# led-panel.net
KiCad netlist of a schematic drawn in EAGLE
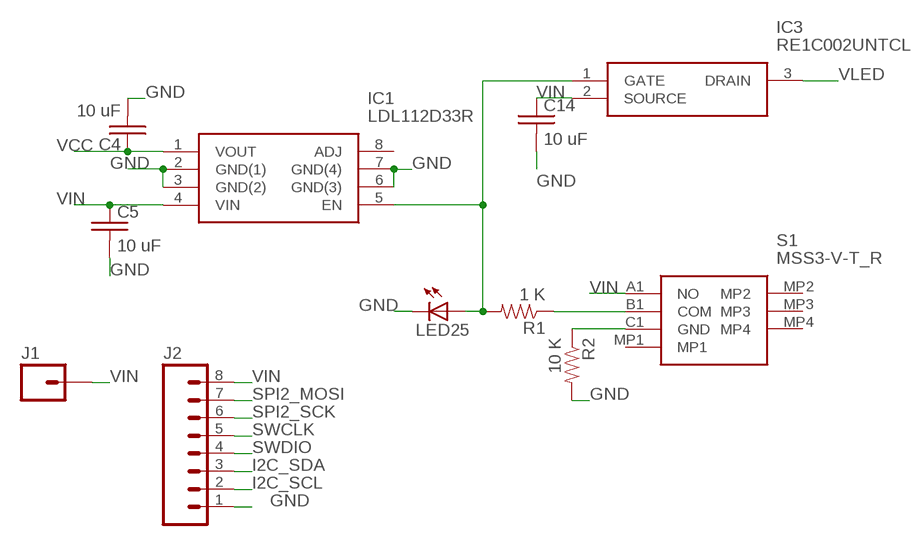
[diagram p0: schematic, sheet 1]
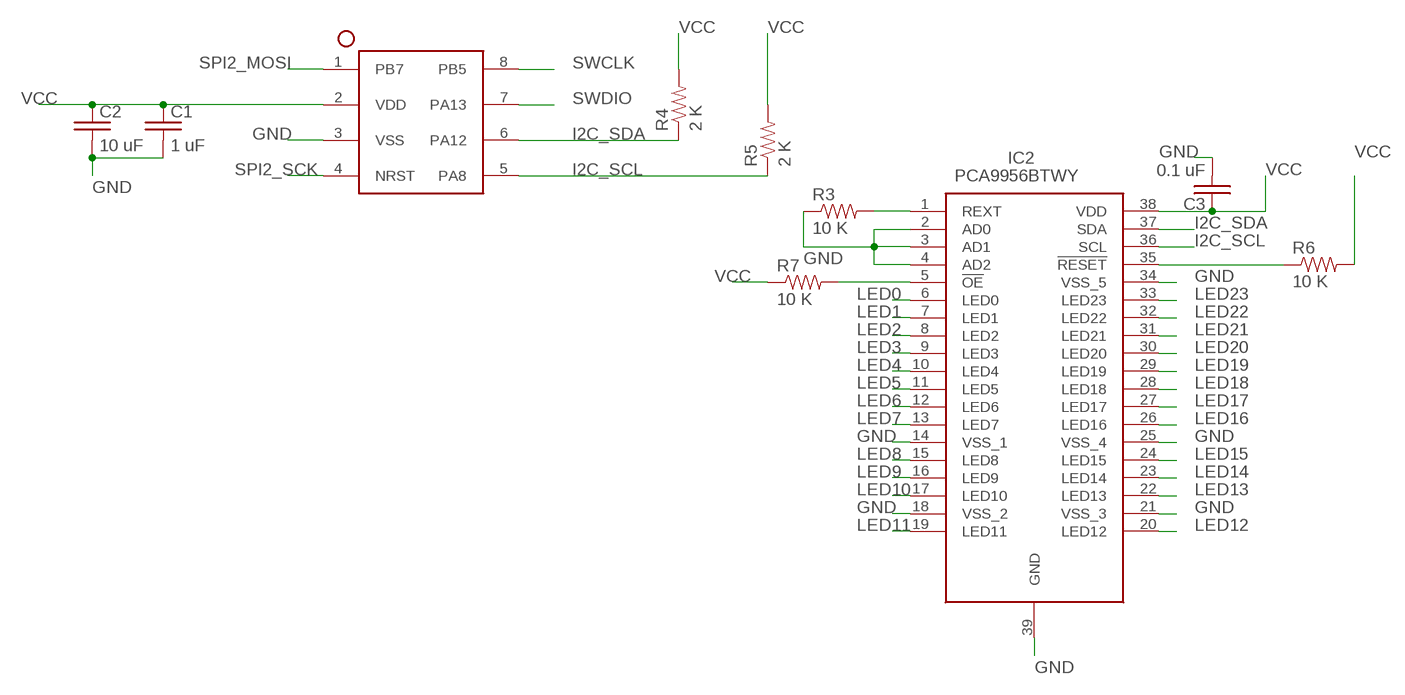
[diagram p1: schematic, sheet 2]
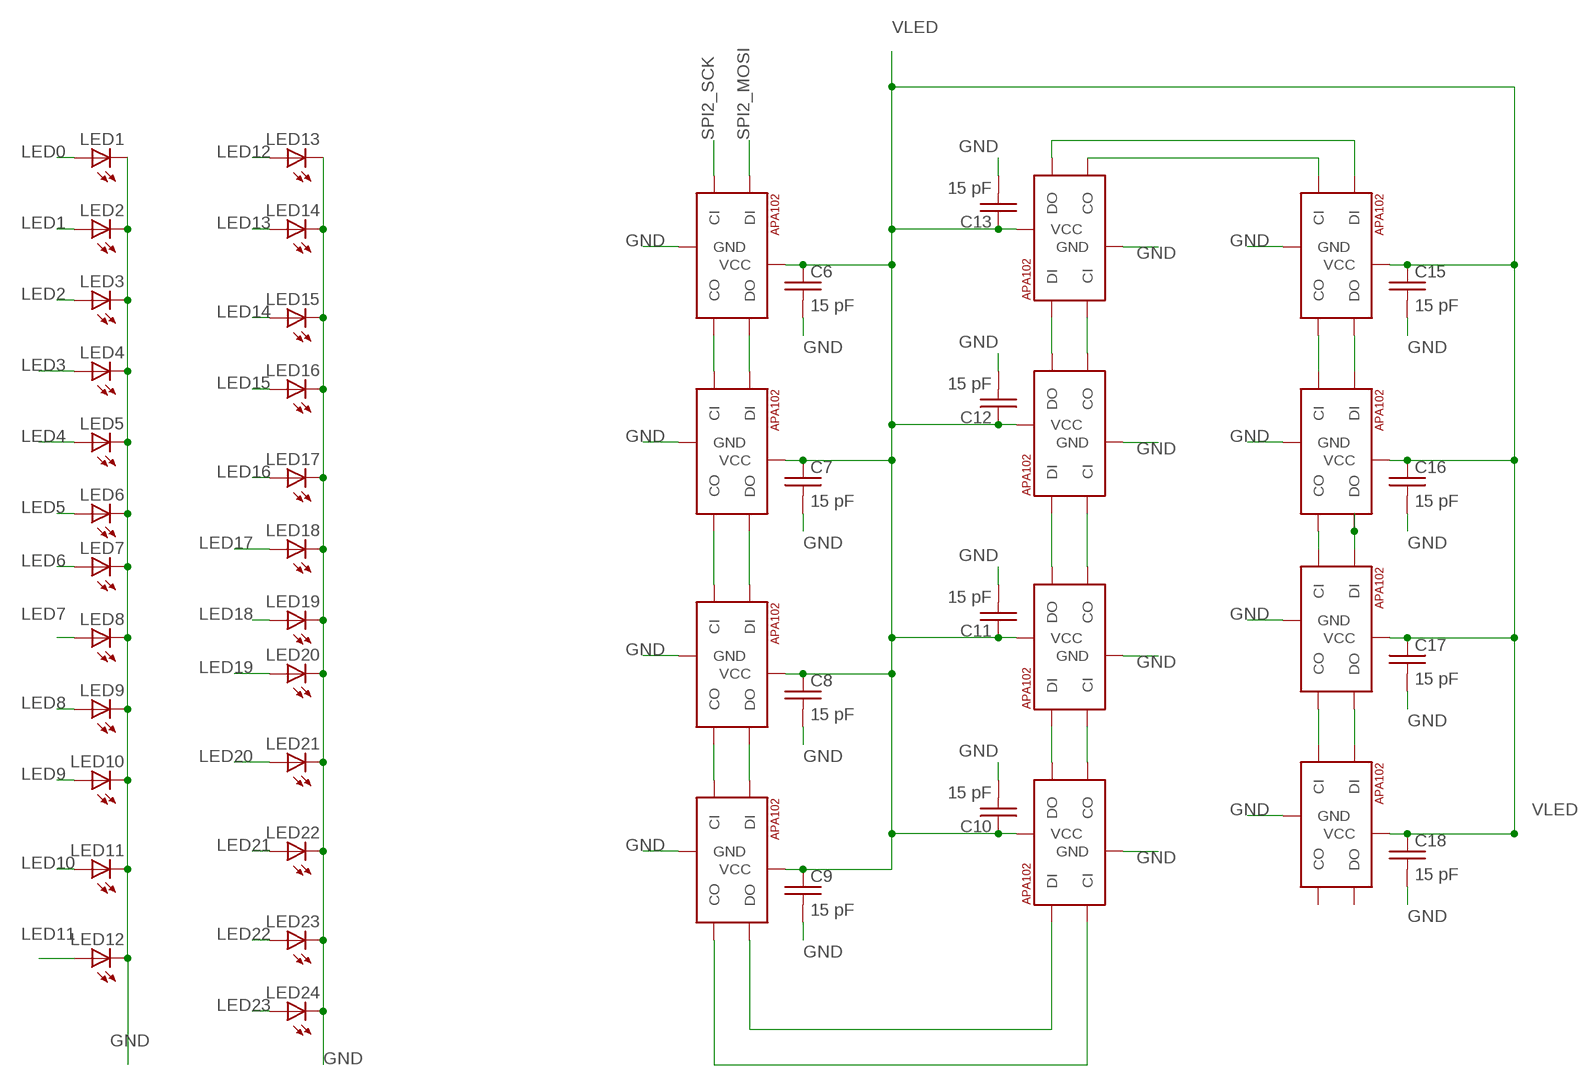
[diagram p2: schematic, sheet 3]
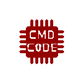
[diagram p3: schematic, sheet 4]

(export (version "E")
  (design (tool "Eeschema 10.0.6"))
  (components
    (comp (ref "U$3")
      (value "CMD_C0DE_LOGOCMD_CODE_LOGO_TOP_COPPER")
      (footprint "eagle-import:CMD_C0DE_LOGO_TOP_COPPER")
      (libsource (lib "eagle-import") (part "CMD_C0DE_LOGOCMD_CODE_LOGO_TOP_COPPER"))
    )
    (comp (ref "C6")
      (value "15 pF")
      (footprint "eagle-import:C0805K")
      (libsource (lib "eagle-import") (part "C-USC0805K"))
    )
    (comp (ref "C7")
      (value "15 pF")
      (footprint "eagle-import:C0805K")
      (libsource (lib "eagle-import") (part "C-USC0805K"))
    )
    (comp (ref "C8")
      (value "15 pF")
      (footprint "eagle-import:C0805K")
      (libsource (lib "eagle-import") (part "C-USC0805K"))
    )
    (comp (ref "C9")
      (value "15 pF")
      (footprint "eagle-import:C0805K")
      (libsource (lib "eagle-import") (part "C-USC0805K"))
    )
    (comp (ref "C10")
      (value "15 pF")
      (footprint "eagle-import:C0805K")
      (libsource (lib "eagle-import") (part "C-USC0805K"))
    )
    (comp (ref "C11")
      (value "15 pF")
      (footprint "eagle-import:C0805K")
      (libsource (lib "eagle-import") (part "C-USC0805K"))
    )
    (comp (ref "C12")
      (value "15 pF")
      (footprint "eagle-import:C0805K")
      (libsource (lib "eagle-import") (part "C-USC0805K"))
    )
    (comp (ref "C13")
      (value "15 pF")
      (footprint "eagle-import:C0805K")
      (libsource (lib "eagle-import") (part "C-USC0805K"))
    )
    (comp (ref "C15")
      (value "15 pF")
      (footprint "eagle-import:C0805K")
      (libsource (lib "eagle-import") (part "C-USC0805K"))
    )
    (comp (ref "C16")
      (value "15 pF")
      (footprint "eagle-import:C0805K")
      (libsource (lib "eagle-import") (part "C-USC0805K"))
    )
    (comp (ref "C17")
      (value "15 pF")
      (footprint "eagle-import:C0805K")
      (libsource (lib "eagle-import") (part "C-USC0805K"))
    )
    (comp (ref "C18")
      (value "15 pF")
      (footprint "eagle-import:C0805K")
      (libsource (lib "eagle-import") (part "C-USC0805K"))
    )
    (comp (ref "LED1")
      (value "LEDXZCFBB53W-8VF-2MA-LED")
      (footprint "eagle-import:LEDC1606X95N")
      (libsource (lib "eagle-import") (part "LEDXZCFBB53W-8VF-2MA-LED"))
    )
    (comp (ref "LED2")
      (value "LEDXZCFBB53W-8VF-2MA-LED")
      (footprint "eagle-import:LEDC1606X95N")
      (libsource (lib "eagle-import") (part "LEDXZCFBB53W-8VF-2MA-LED"))
    )
    (comp (ref "LED3")
      (value "LEDXZCFBB53W-8VF-2MA-LED")
      (footprint "eagle-import:LEDC1606X95N")
      (libsource (lib "eagle-import") (part "LEDXZCFBB53W-8VF-2MA-LED"))
    )
    (comp (ref "LED4")
      (value "LEDXZCFBB53W-8VF-2MA-LED")
      (footprint "eagle-import:LEDC1606X95N")
      (libsource (lib "eagle-import") (part "LEDXZCFBB53W-8VF-2MA-LED"))
    )
    (comp (ref "LED5")
      (value "LEDXZCFBB53W-8VF-2MA-LED")
      (footprint "eagle-import:LEDC1606X95N")
      (libsource (lib "eagle-import") (part "LEDXZCFBB53W-8VF-2MA-LED"))
    )
    (comp (ref "LED6")
      (value "LEDXZCFBB53W-8VF-2MA-LED")
      (footprint "eagle-import:LEDC1606X95N")
      (libsource (lib "eagle-import") (part "LEDXZCFBB53W-8VF-2MA-LED"))
    )
    (comp (ref "LED7")
      (value "LEDXZCFBB53W-8VF-2MA-LED")
      (footprint "eagle-import:LEDC1606X95N")
      (libsource (lib "eagle-import") (part "LEDXZCFBB53W-8VF-2MA-LED"))
    )
    (comp (ref "LED8")
      (value "LEDXZCFBB53W-8VF-2MA-LED")
      (footprint "eagle-import:LEDC1606X95N")
      (libsource (lib "eagle-import") (part "LEDXZCFBB53W-8VF-2MA-LED"))
    )
    (comp (ref "LED9")
      (value "LEDXZCFBB53W-8VF-2MA-LED")
      (footprint "eagle-import:LEDC1606X95N")
      (libsource (lib "eagle-import") (part "LEDXZCFBB53W-8VF-2MA-LED"))
    )
    (comp (ref "LED10")
      (value "LEDXZCFBB53W-8VF-2MA-LED")
      (footprint "eagle-import:LEDC1606X95N")
      (libsource (lib "eagle-import") (part "LEDXZCFBB53W-8VF-2MA-LED"))
    )
    (comp (ref "LED11")
      (value "LEDXZCFBB53W-8VF-2MA-LED")
      (footprint "eagle-import:LEDC1606X95N")
      (libsource (lib "eagle-import") (part "LEDXZCFBB53W-8VF-2MA-LED"))
    )
    (comp (ref "LED12")
      (value "LEDXZCFBB53W-8VF-2MA-LED")
      (footprint "eagle-import:LEDC1606X95N")
      (libsource (lib "eagle-import") (part "LEDXZCFBB53W-8VF-2MA-LED"))
    )
    (comp (ref "LED13")
      (value "LEDXZCFBB53W-8VF-2MA-LED")
      (footprint "eagle-import:LEDC1606X95N")
      (libsource (lib "eagle-import") (part "LEDXZCFBB53W-8VF-2MA-LED"))
    )
    (comp (ref "LED14")
      (value "LEDXZCFBB53W-8VF-2MA-LED")
      (footprint "eagle-import:LEDC1606X95N")
      (libsource (lib "eagle-import") (part "LEDXZCFBB53W-8VF-2MA-LED"))
    )
    (comp (ref "LED15")
      (value "LEDXZCFBB53W-8VF-2MA-LED")
      (footprint "eagle-import:LEDC1606X95N")
      (libsource (lib "eagle-import") (part "LEDXZCFBB53W-8VF-2MA-LED"))
    )
    (comp (ref "LED16")
      (value "LEDXZCFBB53W-8VF-2MA-LED")
      (footprint "eagle-import:LEDC1606X95N")
      (libsource (lib "eagle-import") (part "LEDXZCFBB53W-8VF-2MA-LED"))
    )
    (comp (ref "LED17")
      (value "LEDXZCFBB53W-8VF-2MA-LED")
      (footprint "eagle-import:LEDC1606X95N")
      (libsource (lib "eagle-import") (part "LEDXZCFBB53W-8VF-2MA-LED"))
    )
    (comp (ref "LED18")
      (value "LEDXZCFBB53W-8VF-2MA-LED")
      (footprint "eagle-import:LEDC1606X95N")
      (libsource (lib "eagle-import") (part "LEDXZCFBB53W-8VF-2MA-LED"))
    )
    (comp (ref "LED19")
      (value "LEDXZCFBB53W-8VF-2MA-LED")
      (footprint "eagle-import:LEDC1606X95N")
      (libsource (lib "eagle-import") (part "LEDXZCFBB53W-8VF-2MA-LED"))
    )
    (comp (ref "LED20")
      (value "LEDXZCFBB53W-8VF-2MA-LED")
      (footprint "eagle-import:LEDC1606X95N")
      (libsource (lib "eagle-import") (part "LEDXZCFBB53W-8VF-2MA-LED"))
    )
    (comp (ref "LED21")
      (value "LEDXZCFBB53W-8VF-2MA-LED")
      (footprint "eagle-import:LEDC1606X95N")
      (libsource (lib "eagle-import") (part "LEDXZCFBB53W-8VF-2MA-LED"))
    )
    (comp (ref "LED22")
      (value "LEDXZCFBB53W-8VF-2MA-LED")
      (footprint "eagle-import:LEDC1606X95N")
      (libsource (lib "eagle-import") (part "LEDXZCFBB53W-8VF-2MA-LED"))
    )
    (comp (ref "LED23")
      (value "LEDXZCFBB53W-8VF-2MA-LED")
      (footprint "eagle-import:LEDC1606X95N")
      (libsource (lib "eagle-import") (part "LEDXZCFBB53W-8VF-2MA-LED"))
    )
    (comp (ref "LED24")
      (value "LEDXZCFBB53W-8VF-2MA-LED")
      (footprint "eagle-import:LEDC1606X95N")
      (libsource (lib "eagle-import") (part "LEDXZCFBB53W-8VF-2MA-LED"))
    )
    (comp (ref "U$2")
      (value "APA1025050")
      (footprint "eagle-import:APA102_5050")
      (libsource (lib "eagle-import") (part "APA1025050"))
    )
    (comp (ref "U$4")
      (value "APA1025050")
      (footprint "eagle-import:APA102_5050")
      (libsource (lib "eagle-import") (part "APA1025050"))
    )
    (comp (ref "U$5")
      (value "APA1025050")
      (footprint "eagle-import:APA102_5050")
      (libsource (lib "eagle-import") (part "APA1025050"))
    )
    (comp (ref "U$6")
      (value "APA1025050")
      (footprint "eagle-import:APA102_5050")
      (libsource (lib "eagle-import") (part "APA1025050"))
    )
    (comp (ref "U$7")
      (value "APA1025050")
      (footprint "eagle-import:APA102_5050")
      (libsource (lib "eagle-import") (part "APA1025050"))
    )
    (comp (ref "U$8")
      (value "APA1025050")
      (footprint "eagle-import:APA102_5050")
      (libsource (lib "eagle-import") (part "APA1025050"))
    )
    (comp (ref "U$9")
      (value "APA1025050")
      (footprint "eagle-import:APA102_5050")
      (libsource (lib "eagle-import") (part "APA1025050"))
    )
    (comp (ref "U$10")
      (value "APA1025050")
      (footprint "eagle-import:APA102_5050")
      (libsource (lib "eagle-import") (part "APA1025050"))
    )
    (comp (ref "U$11")
      (value "APA1025050")
      (footprint "eagle-import:APA102_5050")
      (libsource (lib "eagle-import") (part "APA1025050"))
    )
    (comp (ref "U$12")
      (value "APA1025050")
      (footprint "eagle-import:APA102_5050")
      (libsource (lib "eagle-import") (part "APA1025050"))
    )
    (comp (ref "U$13")
      (value "APA1025050")
      (footprint "eagle-import:APA102_5050")
      (libsource (lib "eagle-import") (part "APA1025050"))
    )
    (comp (ref "U$14")
      (value "APA1025050")
      (footprint "eagle-import:APA102_5050")
      (libsource (lib "eagle-import") (part "APA1025050"))
    )
    (comp (ref "C4")
      (value "10 uF")
      (footprint "eagle-import:C0805K")
      (libsource (lib "eagle-import") (part "C-USC0805K"))
    )
    (comp (ref "C5")
      (value "10 uF")
      (footprint "eagle-import:C0805K")
      (libsource (lib "eagle-import") (part "C-USC0805K"))
    )
    (comp (ref "C14")
      (value "10 uF")
      (footprint "eagle-import:C0805K")
      (libsource (lib "eagle-import") (part "C-USC0805K"))
    )
    (comp (ref "IC1")
      (value "LDL112D33R")
      (footprint "eagle-import:SOIC127P600X175-8N")
      (libsource (lib "eagle-import") (part "LDL112D33R"))
    )
    (comp (ref "IC3")
      (value "RE1C002UNTCL")
      (footprint "eagle-import:SOT50P160X85-3N")
      (fields (field (name "MOUSER_PART_NUMBER") "755-RE1C002UNTCL"))
      (libsource (lib "eagle-import") (part "RE1C002UNTCL"))
    )
    (comp (ref "J1")
      (value "M01HVIA")
      (footprint "eagle-import:HOME_VIA")
      (libsource (lib "eagle-import") (part "M01HVIA"))
    )
    (comp (ref "J2")
      (value "M08LONGPADS")
      (footprint "eagle-import:1X08_LONGPADS")
      (libsource (lib "eagle-import") (part "M08LONGPADS"))
    )
    (comp (ref "LED25")
      (value "LEDXZCFBB53W-8VF-2MA-LED")
      (footprint "eagle-import:LEDC1606X95N")
      (libsource (lib "eagle-import") (part "LEDXZCFBB53W-8VF-2MA-LED"))
    )
    (comp (ref "R1")
      (value "1 K")
      (footprint "eagle-import:R0805")
      (libsource (lib "eagle-import") (part "RESISTORR0805-RES"))
    )
    (comp (ref "R2")
      (value "10 K")
      (footprint "eagle-import:R0805")
      (libsource (lib "eagle-import") (part "RESISTORR0805-RES"))
    )
    (comp (ref "S1")
      (value "MSS3-V-T_R")
      (footprint "eagle-import:MSS3VTR")
      (fields
        (field (name "MANUFACTURER_PART_NUMBER") "MSS3-V-T/R")
        (field (name "MOUSER_PART_NUMBER") "113-MSS3-V-T/R")
      )
      (libsource (lib "eagle-import") (part "MSS3-V-T_R"))
    )
    (comp (ref "C1")
      (value "1 uF")
      (footprint "eagle-import:C0805K")
      (libsource (lib "eagle-import") (part "C-USC0805K"))
    )
    (comp (ref "C2")
      (value "10 uF")
      (footprint "eagle-import:C0805K")
      (libsource (lib "eagle-import") (part "C-USC0805K"))
    )
    (comp (ref "C3")
      (value "0.1 uF")
      (footprint "eagle-import:C0805K")
      (libsource (lib "eagle-import") (part "C-USC0805K"))
    )
    (comp (ref "IC2")
      (value "PCA9956BTWY")
      (footprint "eagle-import:SOP50P640X110-39N")
      (fields (field (name "MOUSER_PART_NUMBER") "771-PCA9956BTWY"))
      (libsource (lib "eagle-import") (part "PCA9956BTWY"))
    )
    (comp (ref "R3")
      (value "10 K")
      (footprint "eagle-import:0805")
      (libsource (lib "eagle-import") (part "RESISTOR0805-RES"))
    )
    (comp (ref "R4")
      (value "2 K")
      (footprint "eagle-import:0805")
      (libsource (lib "eagle-import") (part "RESISTOR0805-RES"))
    )
    (comp (ref "R5")
      (value "2 K")
      (footprint "eagle-import:0805")
      (libsource (lib "eagle-import") (part "RESISTOR0805-RES"))
    )
    (comp (ref "R6")
      (value "10 K")
      (footprint "eagle-import:0805")
      (libsource (lib "eagle-import") (part "RESISTOR0805-RES"))
    )
    (comp (ref "R7")
      (value "10 K")
      (footprint "eagle-import:0805")
      (libsource (lib "eagle-import") (part "RESISTOR0805-RES"))
    )
    (comp (ref "U$1")
      (value "STM32G031S08N")
      (footprint "eagle-import:SOIC127P600X175-8N")
      (libsource (lib "eagle-import") (part "STM32G031S08N"))
    )
  )
  (nets
    (net (code "1") (name "GND") (class "Default")
      (node (ref "C1") (pin "2") (pinfunction "2_2") (pintype "passive"))
      (node (ref "C10") (pin "2") (pinfunction "2_2") (pintype "passive"))
      (node (ref "C11") (pin "2") (pinfunction "2_2") (pintype "passive"))
      (node (ref "C12") (pin "2") (pinfunction "2_2") (pintype "passive"))
      (node (ref "C13") (pin "2") (pinfunction "2_2") (pintype "passive"))
      (node (ref "C14") (pin "2") (pinfunction "2_2") (pintype "passive"))
      (node (ref "C15") (pin "2") (pinfunction "2_2") (pintype "passive"))
      (node (ref "C16") (pin "2") (pinfunction "2_2") (pintype "passive"))
      (node (ref "C17") (pin "2") (pinfunction "2_2") (pintype "passive"))
      (node (ref "C18") (pin "2") (pinfunction "2_2") (pintype "passive"))
      (node (ref "C2") (pin "2") (pinfunction "2_2") (pintype "passive"))
      (node (ref "C3") (pin "2") (pinfunction "2_2") (pintype "passive"))
      (node (ref "C4") (pin "2") (pinfunction "2_2") (pintype "passive"))
      (node (ref "C5") (pin "2") (pinfunction "2_2") (pintype "passive"))
      (node (ref "C6") (pin "2") (pinfunction "2_2") (pintype "passive"))
      (node (ref "C7") (pin "2") (pinfunction "2_2") (pintype "passive"))
      (node (ref "C8") (pin "2") (pinfunction "2_2") (pintype "passive"))
      (node (ref "C9") (pin "2") (pinfunction "2_2") (pintype "passive"))
      (node (ref "IC1") (pin "2") (pinfunction "GND(1)_2") (pintype "bidirectional"))
      (node (ref "IC1") (pin "3") (pinfunction "GND(2)_3") (pintype "bidirectional"))
      (node (ref "IC1") (pin "6") (pinfunction "GND(3)_6") (pintype "bidirectional"))
      (node (ref "IC1") (pin "7") (pinfunction "GND(4)_7") (pintype "bidirectional"))
      (node (ref "IC2") (pin "14") (pinfunction "VSS_1_14") (pintype "bidirectional"))
      (node (ref "IC2") (pin "18") (pinfunction "VSS_2_18") (pintype "bidirectional"))
      (node (ref "IC2") (pin "2") (pinfunction "AD0_2") (pintype "bidirectional"))
      (node (ref "IC2") (pin "21") (pinfunction "VSS_3_21") (pintype "bidirectional"))
      (node (ref "IC2") (pin "25") (pinfunction "VSS_4_25") (pintype "bidirectional"))
      (node (ref "IC2") (pin "3") (pinfunction "AD1_3") (pintype "bidirectional"))
      (node (ref "IC2") (pin "34") (pinfunction "VSS_5_34") (pintype "bidirectional"))
      (node (ref "IC2") (pin "39") (pinfunction "GND_39") (pintype "bidirectional"))
      (node (ref "IC2") (pin "4") (pinfunction "AD2_4") (pintype "bidirectional"))
      (node (ref "J2") (pin "1") (pinfunction "1_1") (pintype "passive"))
      (node (ref "LED1") (pin "2") (pinfunction "C_2") (pintype "output"))
      (node (ref "LED10") (pin "2") (pinfunction "C_2") (pintype "output"))
      (node (ref "LED11") (pin "2") (pinfunction "C_2") (pintype "output"))
      (node (ref "LED12") (pin "2") (pinfunction "C_2") (pintype "output"))
      (node (ref "LED13") (pin "2") (pinfunction "C_2") (pintype "output"))
      (node (ref "LED14") (pin "2") (pinfunction "C_2") (pintype "output"))
      (node (ref "LED15") (pin "2") (pinfunction "C_2") (pintype "output"))
      (node (ref "LED16") (pin "2") (pinfunction "C_2") (pintype "output"))
      (node (ref "LED17") (pin "2") (pinfunction "C_2") (pintype "output"))
      (node (ref "LED18") (pin "2") (pinfunction "C_2") (pintype "output"))
      (node (ref "LED19") (pin "2") (pinfunction "C_2") (pintype "output"))
      (node (ref "LED2") (pin "2") (pinfunction "C_2") (pintype "output"))
      (node (ref "LED20") (pin "2") (pinfunction "C_2") (pintype "output"))
      (node (ref "LED21") (pin "2") (pinfunction "C_2") (pintype "output"))
      (node (ref "LED22") (pin "2") (pinfunction "C_2") (pintype "output"))
      (node (ref "LED23") (pin "2") (pinfunction "C_2") (pintype "output"))
      (node (ref "LED24") (pin "2") (pinfunction "C_2") (pintype "output"))
      (node (ref "LED25") (pin "2") (pinfunction "C_2") (pintype "output"))
      (node (ref "LED3") (pin "2") (pinfunction "C_2") (pintype "output"))
      (node (ref "LED4") (pin "2") (pinfunction "C_2") (pintype "output"))
      (node (ref "LED5") (pin "2") (pinfunction "C_2") (pintype "output"))
      (node (ref "LED6") (pin "2") (pinfunction "C_2") (pintype "output"))
      (node (ref "LED7") (pin "2") (pinfunction "C_2") (pintype "output"))
      (node (ref "LED8") (pin "2") (pinfunction "C_2") (pintype "output"))
      (node (ref "LED9") (pin "2") (pinfunction "C_2") (pintype "output"))
      (node (ref "R2") (pin "2") (pinfunction "2_2") (pintype "passive"))
      (node (ref "R3") (pin "1") (pinfunction "1_1") (pintype "passive"))
      (node (ref "U$1") (pin "3") (pinfunction "VSS_3") (pintype "power_in"))
      (node (ref "U$10") (pin "6") (pinfunction "GND_6") (pintype "bidirectional"))
      (node (ref "U$11") (pin "6") (pinfunction "GND_6") (pintype "bidirectional"))
      (node (ref "U$12") (pin "6") (pinfunction "GND_6") (pintype "bidirectional"))
      (node (ref "U$13") (pin "6") (pinfunction "GND_6") (pintype "bidirectional"))
      (node (ref "U$14") (pin "6") (pinfunction "GND_6") (pintype "bidirectional"))
      (node (ref "U$2") (pin "6") (pinfunction "GND_6") (pintype "bidirectional"))
      (node (ref "U$4") (pin "6") (pinfunction "GND_6") (pintype "bidirectional"))
      (node (ref "U$5") (pin "6") (pinfunction "GND_6") (pintype "bidirectional"))
      (node (ref "U$6") (pin "6") (pinfunction "GND_6") (pintype "bidirectional"))
      (node (ref "U$7") (pin "6") (pinfunction "GND_6") (pintype "bidirectional"))
      (node (ref "U$8") (pin "6") (pinfunction "GND_6") (pintype "bidirectional"))
      (node (ref "U$9") (pin "6") (pinfunction "GND_6") (pintype "bidirectional"))
    )
    (net (code "2") (name "I2C_SCL") (class "Default")
      (node (ref "IC2") (pin "36") (pinfunction "SCL_36") (pintype "bidirectional"))
      (node (ref "J2") (pin "2") (pinfunction "2_2") (pintype "passive"))
      (node (ref "R5") (pin "1") (pinfunction "1_1") (pintype "passive"))
      (node (ref "U$1") (pin "5") (pinfunction "PA8_5") (pintype "bidirectional"))
    )
    (net (code "3") (name "I2C_SDA") (class "Default")
      (node (ref "IC2") (pin "37") (pinfunction "SDA_37") (pintype "bidirectional"))
      (node (ref "J2") (pin "3") (pinfunction "3_3") (pintype "passive"))
      (node (ref "R4") (pin "1") (pinfunction "1_1") (pintype "passive"))
      (node (ref "U$1") (pin "6") (pinfunction "PA12_6") (pintype "bidirectional"))
    )
    (net (code "4") (name "LED0") (class "Default")
      (node (ref "IC2") (pin "6") (pinfunction "LED0_6") (pintype "bidirectional"))
      (node (ref "LED1") (pin "1") (pinfunction "A_1") (pintype "input"))
    )
    (net (code "5") (name "LED1") (class "Default")
      (node (ref "IC2") (pin "7") (pinfunction "LED1_7") (pintype "bidirectional"))
      (node (ref "LED2") (pin "1") (pinfunction "A_1") (pintype "input"))
    )
    (net (code "6") (name "LED2") (class "Default")
      (node (ref "IC2") (pin "8") (pinfunction "LED2_8") (pintype "bidirectional"))
      (node (ref "LED3") (pin "1") (pinfunction "A_1") (pintype "input"))
    )
    (net (code "7") (name "LED3") (class "Default")
      (node (ref "IC2") (pin "9") (pinfunction "LED3_9") (pintype "bidirectional"))
      (node (ref "LED4") (pin "1") (pinfunction "A_1") (pintype "input"))
    )
    (net (code "8") (name "LED4") (class "Default")
      (node (ref "IC2") (pin "10") (pinfunction "LED4_10") (pintype "bidirectional"))
      (node (ref "LED5") (pin "1") (pinfunction "A_1") (pintype "input"))
    )
    (net (code "9") (name "LED5") (class "Default")
      (node (ref "IC2") (pin "11") (pinfunction "LED5_11") (pintype "bidirectional"))
      (node (ref "LED6") (pin "1") (pinfunction "A_1") (pintype "input"))
    )
    (net (code "10") (name "LED6") (class "Default")
      (node (ref "IC2") (pin "12") (pinfunction "LED6_12") (pintype "bidirectional"))
      (node (ref "LED7") (pin "1") (pinfunction "A_1") (pintype "input"))
    )
    (net (code "11") (name "LED7") (class "Default")
      (node (ref "IC2") (pin "13") (pinfunction "LED7_13") (pintype "bidirectional"))
      (node (ref "LED8") (pin "1") (pinfunction "A_1") (pintype "input"))
    )
    (net (code "12") (name "LED8") (class "Default")
      (node (ref "IC2") (pin "15") (pinfunction "LED8_15") (pintype "bidirectional"))
      (node (ref "LED9") (pin "1") (pinfunction "A_1") (pintype "input"))
    )
    (net (code "13") (name "LED9") (class "Default")
      (node (ref "IC2") (pin "16") (pinfunction "LED9_16") (pintype "bidirectional"))
      (node (ref "LED10") (pin "1") (pinfunction "A_1") (pintype "input"))
    )
    (net (code "14") (name "LED10") (class "Default")
      (node (ref "IC2") (pin "17") (pinfunction "LED10_17") (pintype "bidirectional"))
      (node (ref "LED11") (pin "1") (pinfunction "A_1") (pintype "input"))
    )
    (net (code "15") (name "LED11") (class "Default")
      (node (ref "IC2") (pin "19") (pinfunction "LED11_19") (pintype "bidirectional"))
      (node (ref "LED12") (pin "1") (pinfunction "A_1") (pintype "input"))
    )
    (net (code "16") (name "LED12") (class "Default")
      (node (ref "IC2") (pin "20") (pinfunction "LED12_20") (pintype "bidirectional"))
      (node (ref "LED13") (pin "1") (pinfunction "A_1") (pintype "input"))
    )
    (net (code "17") (name "LED13") (class "Default")
      (node (ref "IC2") (pin "22") (pinfunction "LED13_22") (pintype "bidirectional"))
      (node (ref "LED14") (pin "1") (pinfunction "A_1") (pintype "input"))
    )
    (net (code "18") (name "LED14") (class "Default")
      (node (ref "IC2") (pin "23") (pinfunction "LED14_23") (pintype "bidirectional"))
      (node (ref "LED15") (pin "1") (pinfunction "A_1") (pintype "input"))
    )
    (net (code "19") (name "LED15") (class "Default")
      (node (ref "IC2") (pin "24") (pinfunction "LED15_24") (pintype "bidirectional"))
      (node (ref "LED16") (pin "1") (pinfunction "A_1") (pintype "input"))
    )
    (net (code "20") (name "LED16") (class "Default")
      (node (ref "IC2") (pin "26") (pinfunction "LED16_26") (pintype "bidirectional"))
      (node (ref "LED17") (pin "1") (pinfunction "A_1") (pintype "input"))
    )
    (net (code "21") (name "LED17") (class "Default")
      (node (ref "IC2") (pin "27") (pinfunction "LED17_27") (pintype "bidirectional"))
      (node (ref "LED18") (pin "1") (pinfunction "A_1") (pintype "input"))
    )
    (net (code "22") (name "LED18") (class "Default")
      (node (ref "IC2") (pin "28") (pinfunction "LED18_28") (pintype "bidirectional"))
      (node (ref "LED19") (pin "1") (pinfunction "A_1") (pintype "input"))
    )
    (net (code "23") (name "LED19") (class "Default")
      (node (ref "IC2") (pin "29") (pinfunction "LED19_29") (pintype "bidirectional"))
      (node (ref "LED20") (pin "1") (pinfunction "A_1") (pintype "input"))
    )
    (net (code "24") (name "LED20") (class "Default")
      (node (ref "IC2") (pin "30") (pinfunction "LED20_30") (pintype "bidirectional"))
      (node (ref "LED21") (pin "1") (pinfunction "A_1") (pintype "input"))
    )
    (net (code "25") (name "LED21") (class "Default")
      (node (ref "IC2") (pin "31") (pinfunction "LED21_31") (pintype "bidirectional"))
      (node (ref "LED22") (pin "1") (pinfunction "A_1") (pintype "input"))
    )
    (net (code "26") (name "LED22") (class "Default")
      (node (ref "IC2") (pin "32") (pinfunction "LED22_32") (pintype "bidirectional"))
      (node (ref "LED23") (pin "1") (pinfunction "A_1") (pintype "input"))
    )
    (net (code "27") (name "LED23") (class "Default")
      (node (ref "IC2") (pin "33") (pinfunction "LED23_33") (pintype "bidirectional"))
      (node (ref "LED24") (pin "1") (pinfunction "A_1") (pintype "input"))
    )
    (net (code "28") (name "Net-(IC1-EN)") (class "Default")
      (node (ref "IC1") (pin "5") (pinfunction "EN_5") (pintype "bidirectional"))
      (node (ref "IC3") (pin "1") (pinfunction "GATE_1") (pintype "bidirectional"))
      (node (ref "LED25") (pin "1") (pinfunction "A_1") (pintype "input"))
      (node (ref "R1") (pin "2") (pinfunction "2_2") (pintype "passive"))
    )
    (net (code "29") (name "Net-(IC2-REXT)") (class "Default")
      (node (ref "IC2") (pin "1") (pinfunction "REXT_1") (pintype "bidirectional"))
      (node (ref "R3") (pin "2") (pinfunction "2_2") (pintype "passive"))
    )
    (net (code "30") (name "Net-(IC2-~{OE})") (class "Default")
      (node (ref "IC2") (pin "5") (pinfunction "~{OE}_5") (pintype "bidirectional"))
      (node (ref "R7") (pin "2") (pinfunction "2_2") (pintype "passive"))
    )
    (net (code "31") (name "Net-(IC2-~{RESET})") (class "Default")
      (node (ref "IC2") (pin "35") (pinfunction "~{RESET}_35") (pintype "bidirectional"))
      (node (ref "R6") (pin "1") (pinfunction "1_1") (pintype "passive"))
    )
    (net (code "32") (name "Net-(S1-COM)") (class "Default")
      (node (ref "R1") (pin "1") (pinfunction "1_1") (pintype "passive"))
      (node (ref "S1") (pin "B1") (pinfunction "COM_B1") (pintype "bidirectional"))
    )
    (net (code "33") (name "Net-(S1-GND)") (class "Default")
      (node (ref "R2") (pin "1") (pinfunction "1_1") (pintype "passive"))
      (node (ref "S1") (pin "C1") (pinfunction "GND_C1") (pintype "bidirectional"))
    )
    (net (code "34") (name "Net-(U$2-CO)") (class "Default")
      (node (ref "U$2") (pin "2") (pinfunction "CO_2") (pintype "bidirectional"))
      (node (ref "U$4") (pin "5") (pinfunction "CI_5") (pintype "bidirectional"))
    )
    (net (code "35") (name "Net-(U$2-DO)") (class "Default")
      (node (ref "U$2") (pin "3") (pinfunction "DO_3") (pintype "bidirectional"))
      (node (ref "U$4") (pin "4") (pinfunction "DI_4") (pintype "bidirectional"))
    )
    (net (code "36") (name "Net-(U$4-CO)") (class "Default")
      (node (ref "U$4") (pin "2") (pinfunction "CO_2") (pintype "bidirectional"))
      (node (ref "U$5") (pin "5") (pinfunction "CI_5") (pintype "bidirectional"))
    )
    (net (code "37") (name "Net-(U$4-DO)") (class "Default")
      (node (ref "U$4") (pin "3") (pinfunction "DO_3") (pintype "bidirectional"))
      (node (ref "U$5") (pin "4") (pinfunction "DI_4") (pintype "bidirectional"))
    )
    (net (code "38") (name "Net-(U$5-CO)") (class "Default")
      (node (ref "U$5") (pin "2") (pinfunction "CO_2") (pintype "bidirectional"))
      (node (ref "U$6") (pin "5") (pinfunction "CI_5") (pintype "bidirectional"))
    )
    (net (code "39") (name "Net-(U$5-DO)") (class "Default")
      (node (ref "U$5") (pin "3") (pinfunction "DO_3") (pintype "bidirectional"))
      (node (ref "U$6") (pin "4") (pinfunction "DI_4") (pintype "bidirectional"))
    )
    (net (code "40") (name "Net-(U$6-CO)") (class "Default")
      (node (ref "U$6") (pin "2") (pinfunction "CO_2") (pintype "bidirectional"))
      (node (ref "U$7") (pin "5") (pinfunction "CI_5") (pintype "bidirectional"))
    )
    (net (code "41") (name "Net-(U$6-DO)") (class "Default")
      (node (ref "U$6") (pin "3") (pinfunction "DO_3") (pintype "bidirectional"))
      (node (ref "U$7") (pin "4") (pinfunction "DI_4") (pintype "bidirectional"))
    )
    (net (code "42") (name "Net-(U$7-CO)") (class "Default")
      (node (ref "U$7") (pin "2") (pinfunction "CO_2") (pintype "bidirectional"))
      (node (ref "U$8") (pin "5") (pinfunction "CI_5") (pintype "bidirectional"))
    )
    (net (code "43") (name "Net-(U$7-DO)") (class "Default")
      (node (ref "U$7") (pin "3") (pinfunction "DO_3") (pintype "bidirectional"))
      (node (ref "U$8") (pin "4") (pinfunction "DI_4") (pintype "bidirectional"))
    )
    (net (code "44") (name "Net-(U$8-CO)") (class "Default")
      (node (ref "U$8") (pin "2") (pinfunction "CO_2") (pintype "bidirectional"))
      (node (ref "U$9") (pin "5") (pinfunction "CI_5") (pintype "bidirectional"))
    )
    (net (code "45") (name "Net-(U$8-DO)") (class "Default")
      (node (ref "U$8") (pin "3") (pinfunction "DO_3") (pintype "bidirectional"))
      (node (ref "U$9") (pin "4") (pinfunction "DI_4") (pintype "bidirectional"))
    )
    (net (code "46") (name "Net-(U$10-CI)") (class "Default")
      (node (ref "U$10") (pin "5") (pinfunction "CI_5") (pintype "bidirectional"))
      (node (ref "U$9") (pin "2") (pinfunction "CO_2") (pintype "bidirectional"))
    )
    (net (code "47") (name "Net-(U$10-CO)") (class "Default")
      (node (ref "U$10") (pin "2") (pinfunction "CO_2") (pintype "bidirectional"))
      (node (ref "U$11") (pin "5") (pinfunction "CI_5") (pintype "bidirectional"))
    )
    (net (code "48") (name "Net-(U$10-DI)") (class "Default")
      (node (ref "U$10") (pin "4") (pinfunction "DI_4") (pintype "bidirectional"))
      (node (ref "U$9") (pin "3") (pinfunction "DO_3") (pintype "bidirectional"))
    )
    (net (code "49") (name "Net-(U$10-DO)") (class "Default")
      (node (ref "U$10") (pin "3") (pinfunction "DO_3") (pintype "bidirectional"))
      (node (ref "U$11") (pin "4") (pinfunction "DI_4") (pintype "bidirectional"))
    )
    (net (code "50") (name "Net-(U$11-CO)") (class "Default")
      (node (ref "U$11") (pin "2") (pinfunction "CO_2") (pintype "bidirectional"))
      (node (ref "U$12") (pin "5") (pinfunction "CI_5") (pintype "bidirectional"))
    )
    (net (code "51") (name "Net-(U$11-DO)") (class "Default")
      (node (ref "U$11") (pin "3") (pinfunction "DO_3") (pintype "bidirectional"))
      (node (ref "U$12") (pin "4") (pinfunction "DI_4") (pintype "bidirectional"))
    )
    (net (code "52") (name "Net-(U$12-CO)") (class "Default")
      (node (ref "U$12") (pin "2") (pinfunction "CO_2") (pintype "bidirectional"))
      (node (ref "U$13") (pin "5") (pinfunction "CI_5") (pintype "bidirectional"))
    )
    (net (code "53") (name "Net-(U$12-DO)") (class "Default")
      (node (ref "U$12") (pin "3") (pinfunction "DO_3") (pintype "bidirectional"))
      (node (ref "U$13") (pin "4") (pinfunction "DI_4") (pintype "bidirectional"))
    )
    (net (code "54") (name "Net-(U$13-CO)") (class "Default")
      (node (ref "U$13") (pin "2") (pinfunction "CO_2") (pintype "bidirectional"))
      (node (ref "U$14") (pin "5") (pinfunction "CI_5") (pintype "bidirectional"))
    )
    (net (code "55") (name "Net-(U$13-DO)") (class "Default")
      (node (ref "U$13") (pin "3") (pinfunction "DO_3") (pintype "bidirectional"))
      (node (ref "U$14") (pin "4") (pinfunction "DI_4") (pintype "bidirectional"))
    )
    (net (code "56") (name "SPI2_MOSI") (class "Default")
      (node (ref "J2") (pin "7") (pinfunction "7_7") (pintype "passive"))
      (node (ref "U$1") (pin "1") (pinfunction "PB7_1") (pintype "bidirectional"))
      (node (ref "U$2") (pin "4") (pinfunction "DI_4") (pintype "bidirectional"))
    )
    (net (code "57") (name "SPI2_SCK") (class "Default")
      (node (ref "J2") (pin "6") (pinfunction "6_6") (pintype "passive"))
      (node (ref "U$1") (pin "4") (pinfunction "NRST_4") (pintype "bidirectional"))
      (node (ref "U$2") (pin "5") (pinfunction "CI_5") (pintype "bidirectional"))
    )
    (net (code "58") (name "SWCLK") (class "Default")
      (node (ref "J2") (pin "5") (pinfunction "5_5") (pintype "passive"))
      (node (ref "U$1") (pin "8") (pinfunction "PB5_8") (pintype "bidirectional"))
    )
    (net (code "59") (name "SWDIO") (class "Default")
      (node (ref "J2") (pin "4") (pinfunction "4_4") (pintype "passive"))
      (node (ref "U$1") (pin "7") (pinfunction "PA13_7") (pintype "bidirectional"))
    )
    (net (code "60") (name "VCC") (class "Default")
      (node (ref "C1") (pin "1") (pinfunction "1_1") (pintype "passive"))
      (node (ref "C2") (pin "1") (pinfunction "1_1") (pintype "passive"))
      (node (ref "C3") (pin "1") (pinfunction "1_1") (pintype "passive"))
      (node (ref "C4") (pin "1") (pinfunction "1_1") (pintype "passive"))
      (node (ref "IC1") (pin "1") (pinfunction "VOUT_1") (pintype "bidirectional"))
      (node (ref "IC2") (pin "38") (pinfunction "VDD_38") (pintype "bidirectional"))
      (node (ref "R4") (pin "2") (pinfunction "2_2") (pintype "passive"))
      (node (ref "R5") (pin "2") (pinfunction "2_2") (pintype "passive"))
      (node (ref "R6") (pin "2") (pinfunction "2_2") (pintype "passive"))
      (node (ref "R7") (pin "1") (pinfunction "1_1") (pintype "passive"))
      (node (ref "U$1") (pin "2") (pinfunction "VDD_2") (pintype "power_in"))
    )
    (net (code "61") (name "VIN") (class "Default")
      (node (ref "C14") (pin "1") (pinfunction "1_1") (pintype "passive"))
      (node (ref "C5") (pin "1") (pinfunction "1_1") (pintype "passive"))
      (node (ref "IC1") (pin "4") (pinfunction "VIN_4") (pintype "bidirectional"))
      (node (ref "IC3") (pin "2") (pinfunction "SOURCE_2") (pintype "bidirectional"))
      (node (ref "J1") (pin "1") (pinfunction "1_1") (pintype "passive"))
      (node (ref "J2") (pin "8") (pinfunction "8_8") (pintype "passive"))
      (node (ref "S1") (pin "A1") (pinfunction "NO_A1") (pintype "bidirectional"))
    )
    (net (code "62") (name "VLED") (class "Default")
      (node (ref "C10") (pin "1") (pinfunction "1_1") (pintype "passive"))
      (node (ref "C11") (pin "1") (pinfunction "1_1") (pintype "passive"))
      (node (ref "C12") (pin "1") (pinfunction "1_1") (pintype "passive"))
      (node (ref "C13") (pin "1") (pinfunction "1_1") (pintype "passive"))
      (node (ref "C15") (pin "1") (pinfunction "1_1") (pintype "passive"))
      (node (ref "C16") (pin "1") (pinfunction "1_1") (pintype "passive"))
      (node (ref "C17") (pin "1") (pinfunction "1_1") (pintype "passive"))
      (node (ref "C18") (pin "1") (pinfunction "1_1") (pintype "passive"))
      (node (ref "C6") (pin "1") (pinfunction "1_1") (pintype "passive"))
      (node (ref "C7") (pin "1") (pinfunction "1_1") (pintype "passive"))
      (node (ref "C8") (pin "1") (pinfunction "1_1") (pintype "passive"))
      (node (ref "C9") (pin "1") (pinfunction "1_1") (pintype "passive"))
      (node (ref "IC3") (pin "3") (pinfunction "DRAIN_3") (pintype "input"))
      (node (ref "U$10") (pin "1") (pinfunction "VCC_1") (pintype "bidirectional"))
      (node (ref "U$11") (pin "1") (pinfunction "VCC_1") (pintype "bidirectional"))
      (node (ref "U$12") (pin "1") (pinfunction "VCC_1") (pintype "bidirectional"))
      (node (ref "U$13") (pin "1") (pinfunction "VCC_1") (pintype "bidirectional"))
      (node (ref "U$14") (pin "1") (pinfunction "VCC_1") (pintype "bidirectional"))
      (node (ref "U$2") (pin "1") (pinfunction "VCC_1") (pintype "bidirectional"))
      (node (ref "U$4") (pin "1") (pinfunction "VCC_1") (pintype "bidirectional"))
      (node (ref "U$5") (pin "1") (pinfunction "VCC_1") (pintype "bidirectional"))
      (node (ref "U$6") (pin "1") (pinfunction "VCC_1") (pintype "bidirectional"))
      (node (ref "U$7") (pin "1") (pinfunction "VCC_1") (pintype "bidirectional"))
      (node (ref "U$8") (pin "1") (pinfunction "VCC_1") (pintype "bidirectional"))
      (node (ref "U$9") (pin "1") (pinfunction "VCC_1") (pintype "bidirectional"))
    )
    (net (code "63") (name "unconnected-(IC1-ADJ-Pad8)") (class "Default")
      (node (ref "IC1") (pin "8") (pinfunction "ADJ_8") (pintype "bidirectional"))
    )
    (net (code "64") (name "unconnected-(S1-PadMP1)") (class "Default")
      (node (ref "S1") (pin "MP1") (pinfunction "MP1_MP1") (pintype "bidirectional"))
    )
    (net (code "65") (name "unconnected-(S1-PadMP2)") (class "Default")
      (node (ref "S1") (pin "MP2") (pinfunction "MP2_MP2") (pintype "bidirectional"))
    )
    (net (code "66") (name "unconnected-(S1-PadMP3)") (class "Default")
      (node (ref "S1") (pin "MP3") (pinfunction "MP3_MP3") (pintype "bidirectional"))
    )
    (net (code "67") (name "unconnected-(S1-PadMP4)") (class "Default")
      (node (ref "S1") (pin "MP4") (pinfunction "MP4_MP4") (pintype "bidirectional"))
    )
    (net (code "68") (name "unconnected-(U$14-CO-Pad2)") (class "Default")
      (node (ref "U$14") (pin "2") (pinfunction "CO_2") (pintype "bidirectional"))
    )
    (net (code "69") (name "unconnected-(U$14-DO-Pad3)") (class "Default")
      (node (ref "U$14") (pin "3") (pinfunction "DO_3") (pintype "bidirectional"))
    )
  )
)
